# AD5791.net
KiCad netlist of a schematic drawn in EAGLE
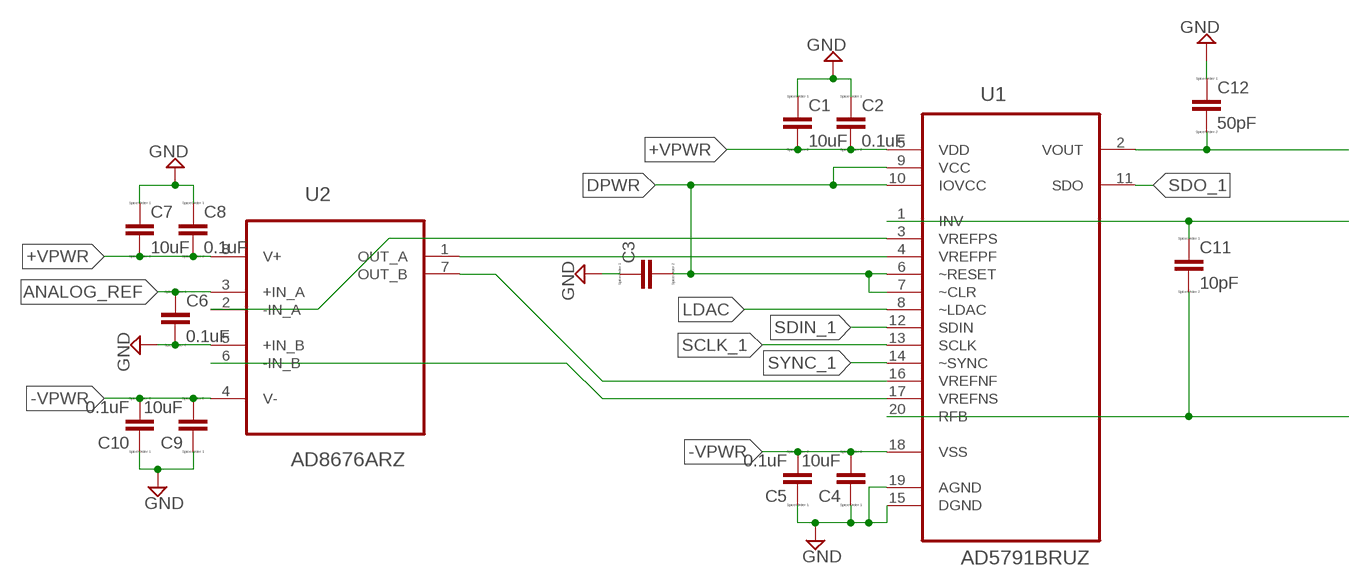
[diagram p0: schematic, sheet 1]

(export (version "E")
  (design (tool "Eeschema 10.0.6"))
  (components
    (comp (ref "C1")
      (value "10uF")
      (footprint "eagle-import:C0805")
      (libsource (lib "eagle-import") (part "C"))
    )
    (comp (ref "C2")
      (value "0.1uF")
      (footprint "eagle-import:C0603")
      (libsource (lib "eagle-import") (part "CC0603"))
    )
    (comp (ref "C3")
      (value "CC0603")
      (footprint "eagle-import:C0603")
      (libsource (lib "eagle-import") (part "CC0603"))
    )
    (comp (ref "C4")
      (value "10uF")
      (footprint "eagle-import:C0805")
      (libsource (lib "eagle-import") (part "C"))
    )
    (comp (ref "C5")
      (value "0.1uF")
      (footprint "eagle-import:C0603")
      (libsource (lib "eagle-import") (part "CC0603"))
    )
    (comp (ref "C6")
      (value "0.1uF")
      (footprint "eagle-import:C0603")
      (libsource (lib "eagle-import") (part "CC0603"))
    )
    (comp (ref "C7")
      (value "10uF")
      (footprint "eagle-import:C0805")
      (libsource (lib "eagle-import") (part "C"))
    )
    (comp (ref "C8")
      (value "0.1uF")
      (footprint "eagle-import:C0603")
      (libsource (lib "eagle-import") (part "CC0603"))
    )
    (comp (ref "C9")
      (value "10uF")
      (footprint "eagle-import:C0805")
      (libsource (lib "eagle-import") (part "C"))
    )
    (comp (ref "C10")
      (value "0.1uF")
      (footprint "eagle-import:C0603")
      (libsource (lib "eagle-import") (part "CC0603"))
    )
    (comp (ref "C11")
      (value "10pF")
      (footprint "eagle-import:C0603")
      (libsource (lib "eagle-import") (part "CC0603"))
    )
    (comp (ref "C12")
      (value "50pF")
      (footprint "eagle-import:C0603")
      (libsource (lib "eagle-import") (part "CC0603"))
    )
    (comp (ref "U1")
      (value "AD5791BRUZ")
      (footprint "eagle-import:SOP65P640X120-20N")
      (libsource (lib "eagle-import") (part "AD5791BRUZ"))
    )
    (comp (ref "U2")
      (value "AD8676ARZ")
      (footprint "eagle-import:SOIC127P600X175-8N")
      (libsource (lib "eagle-import") (part "AD8676ARZ"))
    )
  )
  (nets
    (net (code "1") (name "+VPWR") (class "Default")
      (node (ref "C1") (pin "2") (pinfunction "2_2") (pintype "passive"))
      (node (ref "C2") (pin "2") (pinfunction "2_2") (pintype "passive"))
      (node (ref "C7") (pin "2") (pinfunction "2_2") (pintype "passive"))
      (node (ref "C8") (pin "2") (pinfunction "2_2") (pintype "passive"))
      (node (ref "U1") (pin "5") (pinfunction "VDD_5") (pintype "power_in"))
      (node (ref "U2") (pin "8") (pinfunction "V+_8") (pintype "power_in"))
    )
    (net (code "2") (name "-VPWR") (class "Default")
      (node (ref "C10") (pin "2") (pinfunction "2_2") (pintype "passive"))
      (node (ref "C4") (pin "2") (pinfunction "2_2") (pintype "passive"))
      (node (ref "C5") (pin "2") (pinfunction "2_2") (pintype "passive"))
      (node (ref "C9") (pin "2") (pinfunction "2_2") (pintype "passive"))
      (node (ref "U1") (pin "18") (pinfunction "VSS_18") (pintype "power_in"))
      (node (ref "U2") (pin "4") (pinfunction "V-_4") (pintype "power_in"))
    )
    (net (code "3") (name "ANALOG_REF") (class "Default")
      (node (ref "C6") (pin "1") (pinfunction "1_1") (pintype "passive"))
      (node (ref "U2") (pin "3") (pinfunction "+IN_A_3") (pintype "input"))
    )
    (net (code "4") (name "DPWR") (class "Default")
      (node (ref "C3") (pin "2") (pinfunction "2_2") (pintype "passive"))
      (node (ref "U1") (pin "10") (pinfunction "IOVCC_10") (pintype "power_in"))
      (node (ref "U1") (pin "6") (pinfunction "~{RESET}_6") (pintype "input"))
      (node (ref "U1") (pin "7") (pinfunction "~{CLR}_7") (pintype "input"))
      (node (ref "U1") (pin "9") (pinfunction "VCC_9") (pintype "power_in"))
    )
    (net (code "5") (name "GND") (class "Default")
      (node (ref "C1") (pin "1") (pinfunction "1_1") (pintype "passive"))
      (node (ref "C10") (pin "1") (pinfunction "1_1") (pintype "passive"))
      (node (ref "C12") (pin "1") (pinfunction "1_1") (pintype "passive"))
      (node (ref "C2") (pin "1") (pinfunction "1_1") (pintype "passive"))
      (node (ref "C3") (pin "1") (pinfunction "1_1") (pintype "passive"))
      (node (ref "C4") (pin "1") (pinfunction "1_1") (pintype "passive"))
      (node (ref "C5") (pin "1") (pinfunction "1_1") (pintype "passive"))
      (node (ref "C6") (pin "2") (pinfunction "2_2") (pintype "passive"))
      (node (ref "C7") (pin "1") (pinfunction "1_1") (pintype "passive"))
      (node (ref "C8") (pin "1") (pinfunction "1_1") (pintype "passive"))
      (node (ref "C9") (pin "1") (pinfunction "1_1") (pintype "passive"))
      (node (ref "U1") (pin "15") (pinfunction "DGND_15") (pintype "passive"))
      (node (ref "U1") (pin "19") (pinfunction "AGND_19") (pintype "passive"))
      (node (ref "U2") (pin "5") (pinfunction "+IN_B_5") (pintype "input"))
    )
    (net (code "6") (name "LDAC") (class "Default")
      (node (ref "U1") (pin "8") (pinfunction "~{LDAC}_8") (pintype "input"))
    )
    (net (code "7") (name "Net-(U1-INV)") (class "Default")
      (node (ref "C11") (pin "1") (pinfunction "1_1") (pintype "passive"))
      (node (ref "U1") (pin "1") (pinfunction "INV_1") (pintype "input"))
    )
    (net (code "8") (name "Net-(U1-RFB)") (class "Default")
      (node (ref "C11") (pin "2") (pinfunction "2_2") (pintype "passive"))
      (node (ref "U1") (pin "20") (pinfunction "RFB_20") (pintype "input"))
    )
    (net (code "9") (name "Net-(U1-VOUT)") (class "Default")
      (node (ref "C12") (pin "2") (pinfunction "2_2") (pintype "passive"))
      (node (ref "U1") (pin "2") (pinfunction "VOUT_2") (pintype "output"))
    )
    (net (code "10") (name "Net-(U1-VREFNF)") (class "Default")
      (node (ref "U1") (pin "16") (pinfunction "VREFNF_16") (pintype "input"))
      (node (ref "U2") (pin "7") (pinfunction "OUT_B_7") (pintype "output"))
    )
    (net (code "11") (name "Net-(U1-VREFNS)") (class "Default")
      (node (ref "U1") (pin "17") (pinfunction "VREFNS_17") (pintype "input"))
      (node (ref "U2") (pin "6") (pinfunction "-IN_B_6") (pintype "input"))
    )
    (net (code "12") (name "Net-(U1-VREFPF)") (class "Default")
      (node (ref "U1") (pin "4") (pinfunction "VREFPF_4") (pintype "input"))
      (node (ref "U2") (pin "1") (pinfunction "OUT_A_1") (pintype "output"))
    )
    (net (code "13") (name "Net-(U1-VREFPS)") (class "Default")
      (node (ref "U1") (pin "3") (pinfunction "VREFPS_3") (pintype "input"))
      (node (ref "U2") (pin "2") (pinfunction "-IN_A_2") (pintype "input"))
    )
    (net (code "14") (name "SCLK_1") (class "Default")
      (node (ref "U1") (pin "13") (pinfunction "SCLK_13") (pintype "input"))
    )
    (net (code "15") (name "SDIN_1") (class "Default")
      (node (ref "U1") (pin "12") (pinfunction "SDIN_12") (pintype "input"))
    )
    (net (code "16") (name "SDO_1") (class "Default")
      (node (ref "U1") (pin "11") (pinfunction "SDO_11") (pintype "output"))
    )
    (net (code "17") (name "SYNC_1") (class "Default")
      (node (ref "U1") (pin "14") (pinfunction "~{SYNC}_14") (pintype "input"))
    )
  )
)
